# tumkibot1_7_ICS43434_I_S_Microphone.net
KiCad netlist of a schematic drawn in EasyEDA Pro
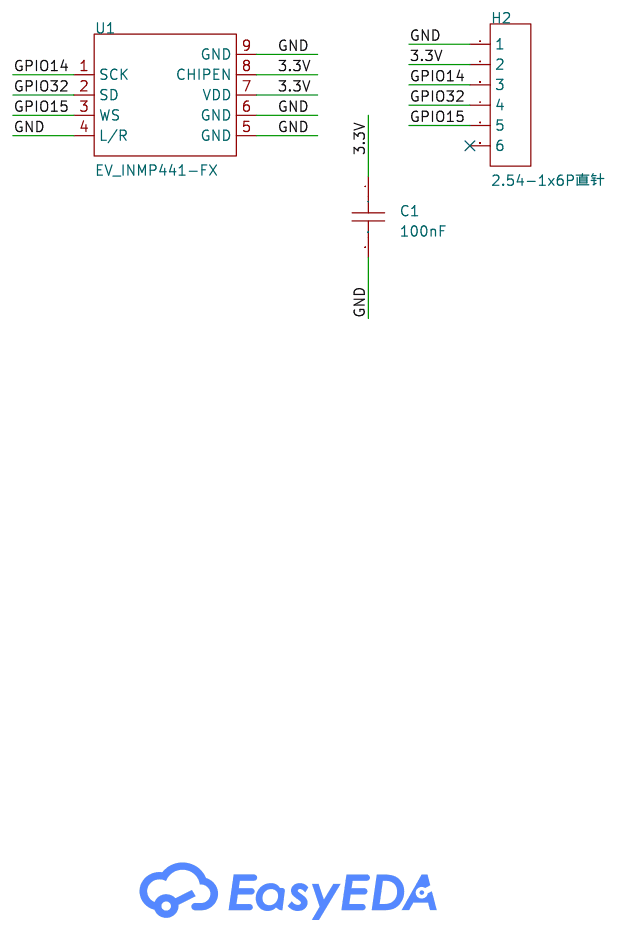
[diagram p0: schematic sheet]

(export (version "E")
  (design (tool "Eeschema 10.0.6"))
  (components
    (comp (ref "C1")
      (value "100nF")
      (footprint "easyedapro:C0603")
      (libsource (lib "easyedapro") (part "CAP"))
    )
    (comp (ref "H2")
      (value "2.54-1x6P直针")
      (footprint "easyedapro:HDR-TH_6P-P2.54-V-M-1")
      (fields (field (name "Manufacturer") "BOOMELE(博穆精密)"))
      (libsource (lib "easyedapro") (part "Header-Male-2.54_1x6"))
    )
    (comp (ref "U1")
      (value "EV_INMP441-FX")
      (footprint "easyedapro:MID-SMD_L4.7-W3.8_INMP441ACEZ")
      (description "Sensor Type:Audio")
      (fields (field (name "Manufacturer") "TDK InvenSense(应美盛)"))
      (libsource (lib "easyedapro") (part "EV_INMP441-FX"))
    )
  )
  (nets
    (net (code "1") (name "/3.3V") (class "Default")
      (node (ref "C1") (pin "1") (pinfunction "1_1") (pintype "input"))
      (node (ref "H2") (pin "2") (pinfunction "2_2") (pintype "input"))
      (node (ref "U1") (pin "7") (pinfunction "VDD_7") (pintype "unspecified"))
      (node (ref "U1") (pin "8") (pinfunction "CHIPEN_8") (pintype "unspecified"))
    )
    (net (code "2") (name "/GND") (class "Default")
      (node (ref "C1") (pin "2") (pinfunction "2_2") (pintype "input"))
      (node (ref "H2") (pin "1") (pinfunction "1_1") (pintype "input"))
      (node (ref "U1") (pin "4") (pinfunction "L/R_4") (pintype "unspecified"))
      (node (ref "U1") (pin "5") (pinfunction "GND_5") (pintype "unspecified"))
      (node (ref "U1") (pin "6") (pinfunction "GND_6") (pintype "unspecified"))
      (node (ref "U1") (pin "9") (pinfunction "GND_9") (pintype "unspecified"))
    )
    (net (code "3") (name "/GPIO14") (class "Default")
      (node (ref "H2") (pin "3") (pinfunction "3_3") (pintype "input"))
      (node (ref "U1") (pin "1") (pinfunction "SCK_1") (pintype "unspecified"))
    )
    (net (code "4") (name "/GPIO15") (class "Default")
      (node (ref "H2") (pin "5") (pinfunction "5_5") (pintype "input"))
      (node (ref "U1") (pin "3") (pinfunction "WS_3") (pintype "unspecified"))
    )
    (net (code "5") (name "/GPIO32") (class "Default")
      (node (ref "H2") (pin "4") (pinfunction "4_4") (pintype "input"))
      (node (ref "U1") (pin "2") (pinfunction "SD_2") (pintype "unspecified"))
    )
    (net (code "6") (name "unconnected-(H2-Pad6)") (class "Default")
      (node (ref "H2") (pin "6") (pinfunction "6_6") (pintype "input+no_connect"))
    )
  )
)
